# LPC1114_--_Valdez_Mutant_v_04.net
KiCad netlist of a schematic drawn in EAGLE
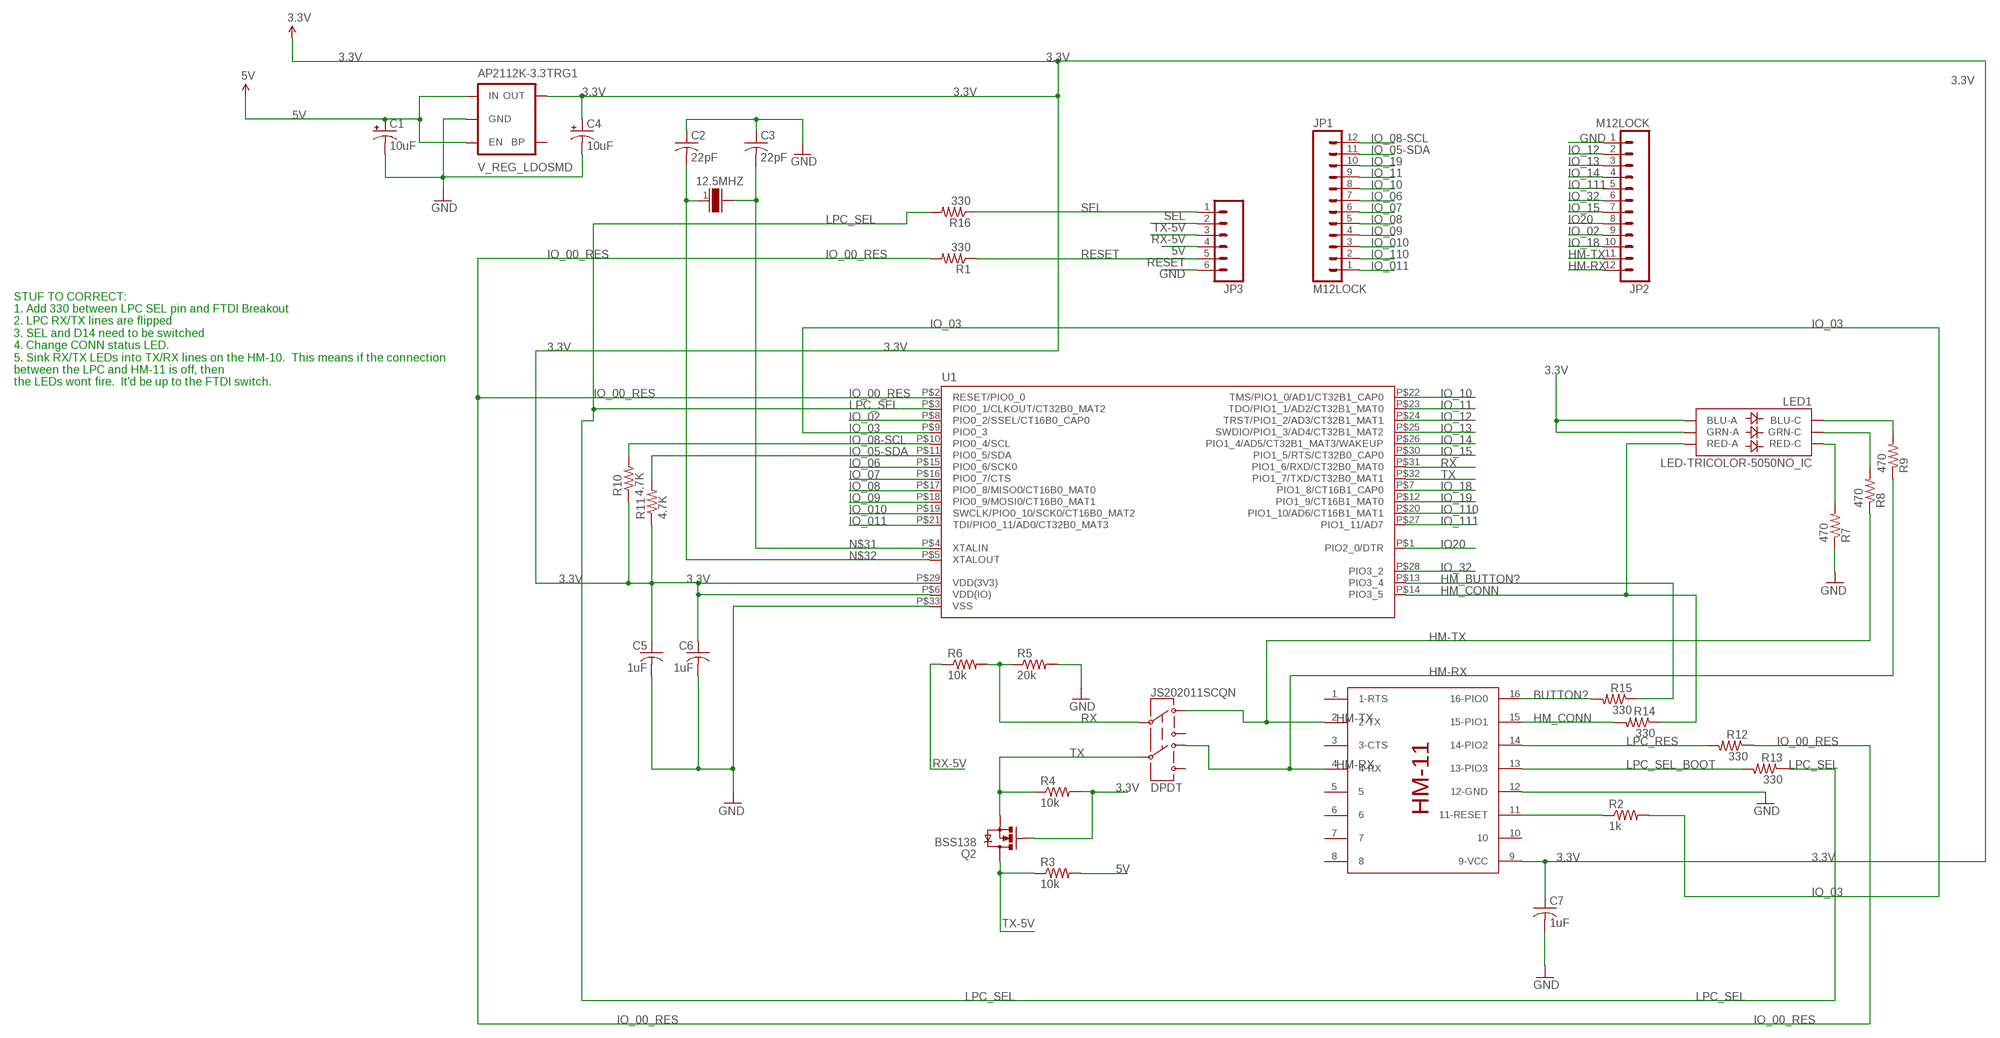
[diagram p0: schematic, sheet 1]

(export (version "E")
  (design (tool "Eeschema 10.0.6"))
  (components
    (comp (ref "12.5MHZ")
      (value "CRYSTAL_SMD_3.2X2.5")
      (footprint "eagle-import:CRYSTAL_SMD_3.2X2.5")
      (libsource (lib "eagle-import") (part "CRYSTAL_SMD_3.2X2.5"))
    )
    (comp (ref "AP2112K-3.3TRG1")
      (value "V_REG_LDOSMD")
      (footprint "eagle-import:SOT23-5")
      (libsource (lib "eagle-import") (part "V_REG_LDOSMD"))
    )
    (comp (ref "C1")
      (value "10uF")
      (footprint "eagle-import:EIA3216")
      (libsource (lib "eagle-import") (part "CAP_POL1206"))
    )
    (comp (ref "C2")
      (value "22pF")
      (footprint "eagle-import:C0402K")
      (libsource (lib "eagle-import") (part "C-USC0402K"))
    )
    (comp (ref "C3")
      (value "22pF")
      (footprint "eagle-import:C0402K")
      (libsource (lib "eagle-import") (part "C-USC0402K"))
    )
    (comp (ref "C4")
      (value "10uF")
      (footprint "eagle-import:EIA3216")
      (libsource (lib "eagle-import") (part "CAP_POL1206"))
    )
    (comp (ref "C5")
      (value "1uF")
      (footprint "eagle-import:C0402K")
      (libsource (lib "eagle-import") (part "C-USC0402K"))
    )
    (comp (ref "C6")
      (value "1uF")
      (footprint "eagle-import:C0402K")
      (libsource (lib "eagle-import") (part "C-USC0402K"))
    )
    (comp (ref "C7")
      (value "1uF")
      (footprint "eagle-import:C0402K")
      (libsource (lib "eagle-import") (part "C-USC0402K"))
    )
    (comp (ref "JP1")
      (value "M12LOCK")
      (footprint "eagle-import:1X12_LOCK")
      (libsource (lib "eagle-import") (part "M12LOCK"))
    )
    (comp (ref "JP2")
      (value "M12LOCK")
      (footprint "eagle-import:1X12_LOCK")
      (libsource (lib "eagle-import") (part "M12LOCK"))
    )
    (comp (ref "JP3")
      (value "M06LOCK")
      (footprint "eagle-import:1X06_LOCK")
      (libsource (lib "eagle-import") (part "M06LOCK"))
    )
    (comp (ref "JS202011SCQN")
      (value "DPDT")
      (footprint "eagle-import:AYZ0202")
      (libsource (lib "eagle-import") (part "SWITCH-DPDTAYZ0202"))
    )
    (comp (ref "LED1")
      (value "LED-TRICOLOR-5050NO_IC")
      (footprint "eagle-import:LED-TRICOLOR-5050")
      (libsource (lib "eagle-import") (part "LED-TRICOLOR-5050NO_IC"))
    )
    (comp (ref "Q2")
      (value "BSS138")
      (footprint "eagle-import:SOT23")
      (libsource (lib "eagle-import") (part "MOSFET-NCHANNELBSS138"))
    )
    (comp (ref "R1")
      (value "330")
      (footprint "eagle-import:R0402")
      (libsource (lib "eagle-import") (part "R-US_R0402"))
    )
    (comp (ref "R2")
      (value "1k")
      (footprint "eagle-import:R0402")
      (libsource (lib "eagle-import") (part "R-US_R0402"))
    )
    (comp (ref "R3")
      (value "10k")
      (footprint "eagle-import:R0402")
      (libsource (lib "eagle-import") (part "R-US_R0402"))
    )
    (comp (ref "R4")
      (value "10k")
      (footprint "eagle-import:R0402")
      (libsource (lib "eagle-import") (part "R-US_R0402"))
    )
    (comp (ref "R5")
      (value "20k")
      (footprint "eagle-import:R0402")
      (libsource (lib "eagle-import") (part "R-US_R0402"))
    )
    (comp (ref "R6")
      (value "10k")
      (footprint "eagle-import:R0402")
      (libsource (lib "eagle-import") (part "R-US_R0402"))
    )
    (comp (ref "R7")
      (value "470")
      (footprint "eagle-import:R0402")
      (libsource (lib "eagle-import") (part "R-US_R0402"))
    )
    (comp (ref "R8")
      (value "470")
      (footprint "eagle-import:R0402")
      (libsource (lib "eagle-import") (part "R-US_R0402"))
    )
    (comp (ref "R9")
      (value "470")
      (footprint "eagle-import:R0402")
      (libsource (lib "eagle-import") (part "R-US_R0402"))
    )
    (comp (ref "R10")
      (value "4.7K")
      (footprint "eagle-import:R0402")
      (libsource (lib "eagle-import") (part "R-US_R0402"))
    )
    (comp (ref "R11")
      (value "4.7K")
      (footprint "eagle-import:R0402")
      (libsource (lib "eagle-import") (part "R-US_R0402"))
    )
    (comp (ref "R12")
      (value "330")
      (footprint "eagle-import:R0402")
      (libsource (lib "eagle-import") (part "R-US_R0402"))
    )
    (comp (ref "R13")
      (value "330")
      (footprint "eagle-import:R0402")
      (libsource (lib "eagle-import") (part "R-US_R0402"))
    )
    (comp (ref "R14")
      (value "330")
      (footprint "eagle-import:R0402")
      (libsource (lib "eagle-import") (part "R-US_R0402"))
    )
    (comp (ref "R15")
      (value "330")
      (footprint "eagle-import:R0402")
      (libsource (lib "eagle-import") (part "R-US_R0402"))
    )
    (comp (ref "R16")
      (value "330")
      (footprint "eagle-import:R0402")
      (libsource (lib "eagle-import") (part "R-US_R0402"))
    )
    (comp (ref "U$1")
      (value "HM-11")
      (footprint "eagle-import:HM-11")
      (libsource (lib "eagle-import") (part "HM-11"))
    )
    (comp (ref "U1")
      (value "LPC1113/4_QFN")
      (footprint "eagle-import:HVQFN33-7X7")
      (fields (field (name "MANF") "NXP"))
      (libsource (lib "eagle-import") (part "LPC1113/4_QFN"))
    )
  )
  (nets
    (net (code "1") (name "/BUTTON?") (class "Default")
      (node (ref "R15") (pin "2") (pinfunction "2_2") (pintype "passive"))
      (node (ref "U$1") (pin "16") (pinfunction "16-PIO0_16") (pintype "bidirectional"))
    )
    (net (code "2") (name "/HM-RX") (class "Default")
      (node (ref "JP2") (pin "12") (pinfunction "12_12") (pintype "passive"))
      (node (ref "JS202011SCQN") (pin "4") (pinfunction "4_4") (pintype "bidirectional"))
      (node (ref "R9") (pin "1") (pinfunction "1_1") (pintype "passive"))
      (node (ref "U$1") (pin "4") (pinfunction "4-RX_4") (pintype "bidirectional"))
    )
    (net (code "3") (name "/HM-TX") (class "Default")
      (node (ref "JP2") (pin "11") (pinfunction "11_11") (pintype "passive"))
      (node (ref "JS202011SCQN") (pin "1") (pinfunction "1_1") (pintype "bidirectional"))
      (node (ref "R8") (pin "1") (pinfunction "1_1") (pintype "passive"))
      (node (ref "U$1") (pin "2") (pinfunction "2-TX_2") (pintype "bidirectional"))
    )
    (net (code "4") (name "/HM_BUTTON?") (class "Default")
      (node (ref "R15") (pin "1") (pinfunction "1_1") (pintype "passive"))
      (node (ref "U1") (pin "P$13") (pinfunction "PIO3_4_P$13") (pintype "bidirectional"))
    )
    (net (code "5") (name "/HM_CONN") (class "Default")
      (node (ref "LED1") (pin "2") (pinfunction "RED-A_2") (pintype "bidirectional"))
      (node (ref "R14") (pin "1") (pinfunction "1_1") (pintype "passive"))
      (node (ref "U1") (pin "P$14") (pinfunction "PIO3_5_P$14") (pintype "bidirectional"))
    )
    (net (code "6") (name "/IO20") (class "Default")
      (node (ref "JP2") (pin "8") (pinfunction "8_8") (pintype "passive"))
      (node (ref "U1") (pin "P$1") (pinfunction "PIO2_0/DTR_P$1") (pintype "bidirectional"))
    )
    (net (code "7") (name "/IO_00_RES") (class "Default")
      (node (ref "R1") (pin "2") (pinfunction "2_2") (pintype "passive"))
      (node (ref "R12") (pin "1") (pinfunction "1_1") (pintype "passive"))
      (node (ref "U1") (pin "P$2") (pinfunction "RESET/PIO0_0_P$2") (pintype "bidirectional"))
    )
    (net (code "8") (name "/IO_02") (class "Default")
      (node (ref "JP2") (pin "9") (pinfunction "9_9") (pintype "passive"))
      (node (ref "U1") (pin "P$8") (pinfunction "PIO0_2/SSEL/CT16B0_CAP0_P$8") (pintype "bidirectional"))
    )
    (net (code "9") (name "/IO_03") (class "Default")
      (node (ref "R2") (pin "2") (pinfunction "2_2") (pintype "passive"))
      (node (ref "U1") (pin "P$9") (pinfunction "PIO0_3_P$9") (pintype "bidirectional"))
    )
    (net (code "10") (name "/IO_05-SDA") (class "Default")
      (node (ref "JP1") (pin "11") (pinfunction "11_11") (pintype "passive"))
      (node (ref "R11") (pin "2") (pinfunction "2_2") (pintype "passive"))
      (node (ref "U1") (pin "P$11") (pinfunction "PIO0_5/SDA_P$11") (pintype "bidirectional"))
    )
    (net (code "11") (name "/IO_06") (class "Default")
      (node (ref "JP1") (pin "7") (pinfunction "7_7") (pintype "passive"))
      (node (ref "U1") (pin "P$15") (pinfunction "PIO0_6/SCK0_P$15") (pintype "bidirectional"))
    )
    (net (code "12") (name "/IO_07") (class "Default")
      (node (ref "JP1") (pin "6") (pinfunction "6_6") (pintype "passive"))
      (node (ref "U1") (pin "P$16") (pinfunction "PIO0_7/CTS_P$16") (pintype "bidirectional"))
    )
    (net (code "13") (name "/IO_08") (class "Default")
      (node (ref "JP1") (pin "5") (pinfunction "5_5") (pintype "passive"))
      (node (ref "U1") (pin "P$17") (pinfunction "PIO0_8/MISO0/CT16B0_MAT0_P$17") (pintype "bidirectional"))
    )
    (net (code "14") (name "/IO_08-SCL") (class "Default")
      (node (ref "JP1") (pin "12") (pinfunction "12_12") (pintype "passive"))
      (node (ref "R10") (pin "2") (pinfunction "2_2") (pintype "passive"))
      (node (ref "U1") (pin "P$10") (pinfunction "PIO0_4/SCL_P$10") (pintype "bidirectional"))
    )
    (net (code "15") (name "/IO_09") (class "Default")
      (node (ref "JP1") (pin "4") (pinfunction "4_4") (pintype "passive"))
      (node (ref "U1") (pin "P$18") (pinfunction "PIO0_9/MOSI0/CT16B0_MAT1_P$18") (pintype "bidirectional"))
    )
    (net (code "16") (name "/IO_010") (class "Default")
      (node (ref "JP1") (pin "3") (pinfunction "3_3") (pintype "passive"))
      (node (ref "U1") (pin "P$19") (pinfunction "SWCLK/PIO0_10/SCK0/CT16B0_MAT2_P$19") (pintype "bidirectional"))
    )
    (net (code "17") (name "/IO_10") (class "Default")
      (node (ref "JP1") (pin "8") (pinfunction "8_8") (pintype "passive"))
      (node (ref "U1") (pin "P$22") (pinfunction "TMS/PIO1_0/AD1/CT32B1_CAP0_P$22") (pintype "bidirectional"))
    )
    (net (code "18") (name "/IO_011") (class "Default")
      (node (ref "JP1") (pin "1") (pinfunction "1_1") (pintype "passive"))
      (node (ref "U1") (pin "P$21") (pinfunction "TDI/PIO0_11/AD0/CT32B0_MAT3_P$21") (pintype "bidirectional"))
    )
    (net (code "19") (name "/IO_11") (class "Default")
      (node (ref "JP1") (pin "9") (pinfunction "9_9") (pintype "passive"))
      (node (ref "U1") (pin "P$23") (pinfunction "TDO/PIO1_1/AD2/CT32B1_MAT0_P$23") (pintype "bidirectional"))
    )
    (net (code "20") (name "/IO_12") (class "Default")
      (node (ref "JP2") (pin "2") (pinfunction "2_2") (pintype "passive"))
      (node (ref "U1") (pin "P$24") (pinfunction "TRST/PIO1_2/AD3/CT32B1_MAT1_P$24") (pintype "bidirectional"))
    )
    (net (code "21") (name "/IO_13") (class "Default")
      (node (ref "JP2") (pin "3") (pinfunction "3_3") (pintype "passive"))
      (node (ref "U1") (pin "P$25") (pinfunction "SWDIO/PIO1_3/AD4/CT32B1_MAT2_P$25") (pintype "bidirectional"))
    )
    (net (code "22") (name "/IO_14") (class "Default")
      (node (ref "JP2") (pin "4") (pinfunction "4_4") (pintype "passive"))
      (node (ref "U1") (pin "P$26") (pinfunction "PIO1_4/AD5/CT32B1_MAT3/WAKEUP_P$26") (pintype "bidirectional"))
    )
    (net (code "23") (name "/IO_15") (class "Default")
      (node (ref "JP2") (pin "7") (pinfunction "7_7") (pintype "passive"))
      (node (ref "U1") (pin "P$30") (pinfunction "PIO1_5/RTS/CT32B0_CAP0_P$30") (pintype "bidirectional"))
    )
    (net (code "24") (name "/IO_18") (class "Default")
      (node (ref "JP2") (pin "10") (pinfunction "10_10") (pintype "passive"))
      (node (ref "U1") (pin "P$7") (pinfunction "PIO1_8/CT16B1_CAP0_P$7") (pintype "bidirectional"))
    )
    (net (code "25") (name "/IO_19") (class "Default")
      (node (ref "JP1") (pin "10") (pinfunction "10_10") (pintype "passive"))
      (node (ref "U1") (pin "P$12") (pinfunction "PIO1_9/CT16B1_MAT0_P$12") (pintype "bidirectional"))
    )
    (net (code "26") (name "/IO_32") (class "Default")
      (node (ref "JP2") (pin "6") (pinfunction "6_6") (pintype "passive"))
      (node (ref "U1") (pin "P$28") (pinfunction "PIO3_2_P$28") (pintype "bidirectional"))
    )
    (net (code "27") (name "/IO_110") (class "Default")
      (node (ref "JP1") (pin "2") (pinfunction "2_2") (pintype "passive"))
      (node (ref "U1") (pin "P$20") (pinfunction "PIO1_10/AD6/CT16B1_MAT1_P$20") (pintype "bidirectional"))
    )
    (net (code "28") (name "/IO_111") (class "Default")
      (node (ref "JP2") (pin "5") (pinfunction "5_5") (pintype "passive"))
      (node (ref "U1") (pin "P$27") (pinfunction "PIO1_11/AD7_P$27") (pintype "bidirectional"))
    )
    (net (code "29") (name "/LPC_RES") (class "Default")
      (node (ref "R12") (pin "2") (pinfunction "2_2") (pintype "passive"))
      (node (ref "U$1") (pin "14") (pinfunction "14-PIO2_14") (pintype "bidirectional"))
    )
    (net (code "30") (name "/LPC_SEL") (class "Default")
      (node (ref "R13") (pin "1") (pinfunction "1_1") (pintype "passive"))
      (node (ref "R16") (pin "2") (pinfunction "2_2") (pintype "passive"))
      (node (ref "U1") (pin "P$3") (pinfunction "PIO0_1/CLKOUT/CT32B0_MAT2_P$3") (pintype "bidirectional"))
    )
    (net (code "31") (name "/LPC_SEL_BOOT") (class "Default")
      (node (ref "R13") (pin "2") (pinfunction "2_2") (pintype "passive"))
      (node (ref "U$1") (pin "13") (pinfunction "13-PIO3_13") (pintype "bidirectional"))
    )
    (net (code "32") (name "/N$31") (class "Default")
      (node (ref "12.5MHZ") (pin "3") (pinfunction "3_3") (pintype "bidirectional"))
      (node (ref "C3") (pin "2") (pinfunction "2_2") (pintype "passive"))
      (node (ref "U1") (pin "P$4") (pinfunction "XTALIN_P$4") (pintype "input"))
    )
    (net (code "33") (name "/N$32") (class "Default")
      (node (ref "12.5MHZ") (pin "1") (pinfunction "1_1") (pintype "bidirectional"))
      (node (ref "C2") (pin "2") (pinfunction "2_2") (pintype "passive"))
      (node (ref "U1") (pin "P$5") (pinfunction "XTALOUT_P$5") (pintype "output"))
    )
    (net (code "34") (name "/RESET") (class "Default")
      (node (ref "JP3") (pin "5") (pinfunction "5_5") (pintype "passive"))
      (node (ref "R1") (pin "1") (pinfunction "1_1") (pintype "passive"))
    )
    (net (code "35") (name "/RX") (class "Default")
      (node (ref "JS202011SCQN") (pin "2") (pinfunction "2_2") (pintype "bidirectional"))
      (node (ref "R5") (pin "1") (pinfunction "1_1") (pintype "passive"))
      (node (ref "R6") (pin "2") (pinfunction "2_2") (pintype "passive"))
      (node (ref "U1") (pin "P$31") (pinfunction "PIO1_6/RXD/CT32B0_MAT0_P$31") (pintype "bidirectional"))
    )
    (net (code "36") (name "/RX-5V") (class "Default")
      (node (ref "JP3") (pin "3") (pinfunction "3_3") (pintype "passive"))
      (node (ref "R6") (pin "1") (pinfunction "1_1") (pintype "passive"))
    )
    (net (code "37") (name "/SEL") (class "Default")
      (node (ref "JP3") (pin "1") (pinfunction "1_1") (pintype "passive"))
      (node (ref "R16") (pin "1") (pinfunction "1_1") (pintype "passive"))
    )
    (net (code "38") (name "/TX") (class "Default")
      (node (ref "JS202011SCQN") (pin "5") (pinfunction "5_5") (pintype "bidirectional"))
      (node (ref "Q2") (pin "2") (pinfunction "S_2") (pintype "passive"))
      (node (ref "R4") (pin "1") (pinfunction "1_1") (pintype "passive"))
      (node (ref "U1") (pin "P$32") (pinfunction "PIO1_7/TXD/CT32B0_MAT1_P$32") (pintype "bidirectional"))
    )
    (net (code "39") (name "/TX-5V") (class "Default")
      (node (ref "JP3") (pin "2") (pinfunction "2_2") (pintype "passive"))
      (node (ref "Q2") (pin "3") (pinfunction "D_3") (pintype "passive"))
      (node (ref "R3") (pin "1") (pinfunction "1_1") (pintype "passive"))
    )
    (net (code "40") (name "3.3V") (class "Default")
      (node (ref "AP2112K-3.3TRG1") (pin "5") (pinfunction "OUT_5") (pintype "passive"))
      (node (ref "C4") (pin "A") (pinfunction "+_A") (pintype "passive"))
      (node (ref "C5") (pin "1") (pinfunction "1_1") (pintype "passive"))
      (node (ref "C6") (pin "1") (pinfunction "1_1") (pintype "passive"))
      (node (ref "C7") (pin "1") (pinfunction "1_1") (pintype "passive"))
      (node (ref "LED1") (pin "1") (pinfunction "GRN-A_1") (pintype "bidirectional"))
      (node (ref "LED1") (pin "3") (pinfunction "BLU-A_3") (pintype "bidirectional"))
      (node (ref "Q2") (pin "1") (pinfunction "G_1") (pintype "passive"))
      (node (ref "R10") (pin "1") (pinfunction "1_1") (pintype "passive"))
      (node (ref "R11") (pin "1") (pinfunction "1_1") (pintype "passive"))
      (node (ref "R4") (pin "2") (pinfunction "2_2") (pintype "passive"))
      (node (ref "U$1") (pin "9") (pinfunction "9-VCC_9") (pintype "bidirectional"))
      (node (ref "U1") (pin "P$29") (pinfunction "VDD(3V3)_P$29") (pintype "power_in"))
      (node (ref "U1") (pin "P$6") (pinfunction "VDD(IO)_P$6") (pintype "power_in"))
    )
    (net (code "41") (name "5V") (class "Default")
      (node (ref "AP2112K-3.3TRG1") (pin "1") (pinfunction "IN_1") (pintype "input"))
      (node (ref "AP2112K-3.3TRG1") (pin "3") (pinfunction "EN_3") (pintype "input"))
      (node (ref "C1") (pin "A") (pinfunction "+_A") (pintype "passive"))
      (node (ref "JP3") (pin "4") (pinfunction "4_4") (pintype "passive"))
      (node (ref "R3") (pin "2") (pinfunction "2_2") (pintype "passive"))
    )
    (net (code "42") (name "GND") (class "Default")
      (node (ref "AP2112K-3.3TRG1") (pin "2") (pinfunction "GND_2") (pintype "input"))
      (node (ref "C1") (pin "C") (pinfunction "-_C") (pintype "passive"))
      (node (ref "C2") (pin "1") (pinfunction "1_1") (pintype "passive"))
      (node (ref "C3") (pin "1") (pinfunction "1_1") (pintype "passive"))
      (node (ref "C4") (pin "C") (pinfunction "-_C") (pintype "passive"))
      (node (ref "C5") (pin "2") (pinfunction "2_2") (pintype "passive"))
      (node (ref "C6") (pin "2") (pinfunction "2_2") (pintype "passive"))
      (node (ref "C7") (pin "2") (pinfunction "2_2") (pintype "passive"))
      (node (ref "JP2") (pin "1") (pinfunction "1_1") (pintype "passive"))
      (node (ref "JP3") (pin "6") (pinfunction "6_6") (pintype "passive"))
      (node (ref "R5") (pin "2") (pinfunction "2_2") (pintype "passive"))
      (node (ref "R7") (pin "1") (pinfunction "1_1") (pintype "passive"))
      (node (ref "U$1") (pin "12") (pinfunction "12-GND_12") (pintype "bidirectional"))
      (node (ref "U1") (pin "P$33") (pinfunction "VSS_P$33") (pintype "power_in"))
    )
    (net (code "43") (name "Net-(LED1-BLU-C)") (class "Default")
      (node (ref "LED1") (pin "4") (pinfunction "BLU-C_4") (pintype "bidirectional"))
      (node (ref "R9") (pin "2") (pinfunction "2_2") (pintype "passive"))
    )
    (net (code "44") (name "Net-(LED1-GRN-C)") (class "Default")
      (node (ref "LED1") (pin "6") (pinfunction "GRN-C_6") (pintype "bidirectional"))
      (node (ref "R8") (pin "2") (pinfunction "2_2") (pintype "passive"))
    )
    (net (code "45") (name "Net-(LED1-RED-C)") (class "Default")
      (node (ref "LED1") (pin "5") (pinfunction "RED-C_5") (pintype "bidirectional"))
      (node (ref "R7") (pin "2") (pinfunction "2_2") (pintype "passive"))
    )
    (net (code "46") (name "Net-(U$1-11-RESET)") (class "Default")
      (node (ref "R2") (pin "1") (pinfunction "1_1") (pintype "passive"))
      (node (ref "U$1") (pin "11") (pinfunction "11-RESET_11") (pintype "bidirectional"))
    )
    (net (code "47") (name "Net-(U$1-15-PIO1)") (class "Default")
      (node (ref "R14") (pin "2") (pinfunction "2_2") (pintype "passive"))
      (node (ref "U$1") (pin "15") (pinfunction "15-PIO1_15") (pintype "bidirectional"))
    )
    (net (code "48") (name "unconnected-(AP2112K-3.3TRG1-BP-Pad4)") (class "Default")
      (node (ref "AP2112K-3.3TRG1") (pin "4") (pinfunction "BP_4") (pintype "input"))
    )
    (net (code "49") (name "unconnected-(JS202011SCQN-Pad3)") (class "Default")
      (node (ref "JS202011SCQN") (pin "3") (pinfunction "3_3") (pintype "bidirectional"))
    )
    (net (code "50") (name "unconnected-(JS202011SCQN-Pad6)") (class "Default")
      (node (ref "JS202011SCQN") (pin "6") (pinfunction "6_6") (pintype "bidirectional"))
    )
    (net (code "51") (name "unconnected-(U$1-1-RTS-Pad1)") (class "Default")
      (node (ref "U$1") (pin "1") (pinfunction "1-RTS_1") (pintype "bidirectional"))
    )
    (net (code "52") (name "unconnected-(U$1-3-CTS-Pad3)") (class "Default")
      (node (ref "U$1") (pin "3") (pinfunction "3-CTS_3") (pintype "bidirectional"))
    )
    (net (code "53") (name "unconnected-(U$1-Pad5)") (class "Default")
      (node (ref "U$1") (pin "5") (pinfunction "5_5") (pintype "bidirectional"))
    )
    (net (code "54") (name "unconnected-(U$1-Pad6)") (class "Default")
      (node (ref "U$1") (pin "6") (pinfunction "6_6") (pintype "bidirectional"))
    )
    (net (code "55") (name "unconnected-(U$1-Pad7)") (class "Default")
      (node (ref "U$1") (pin "7") (pinfunction "7_7") (pintype "bidirectional"))
    )
    (net (code "56") (name "unconnected-(U$1-Pad8)") (class "Default")
      (node (ref "U$1") (pin "8") (pinfunction "8_8") (pintype "bidirectional"))
    )
    (net (code "57") (name "unconnected-(U$1-Pad10)") (class "Default")
      (node (ref "U$1") (pin "10") (pinfunction "10_10") (pintype "bidirectional"))
    )
  )
)
